# DCI_MCU_Power.net
KiCad netlist of a schematic drawn in Altium Designer
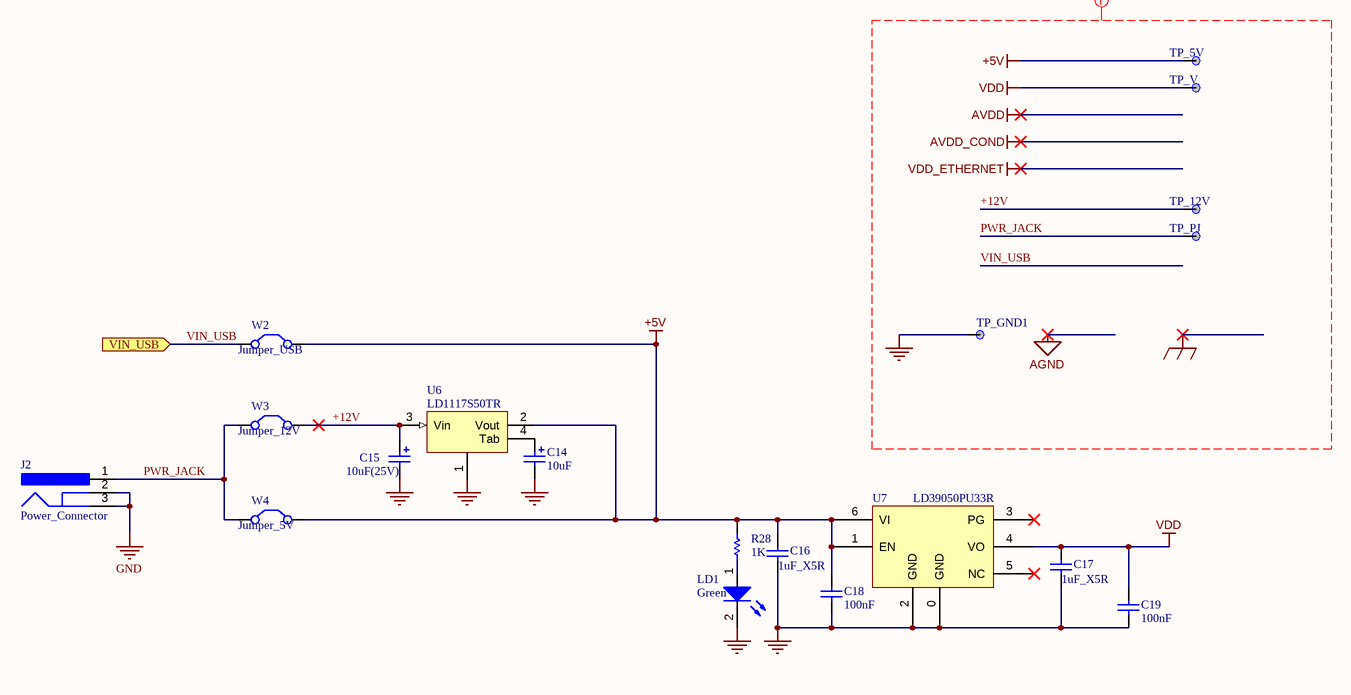
[diagram p0: DCI_MCU_Power.SchDoc]

(export (version "E")
  (design (tool "Eeschema 10.0.6"))
  (components
    (comp (ref "C14")
      (value "10uF")
      (footprint "TAN-A - XDown")
      (description "Polarized Capacitor (Radial)")
      (fields (field (name "PUBLISHER") "Altium Limited"))
      (libsource (lib "Miscellaneous Devices") (part "Cap Pol1"))
    )
    (comp (ref "C15")
      (value "10uF(25V)")
      (footprint "TAN-B")
      (description "Polarized Capacitor (Radial)")
      (fields (field (name "PUBLISHER") "Altium Limited"))
      (libsource (lib "Miscellaneous Devices") (part "Cap Pol1"))
    )
    (comp (ref "C16")
      (value "1uF_X5R")
      (footprint "0603C")
      (description "0603  X5R 1µF")
      (fields (field (name "TOLERANCE") "10%"))
      (libsource (lib "MB963_1") (part "CAP SMD 0603  X5R 1µF 25V 10%"))
    )
    (comp (ref "C17")
      (value "1uF_X5R")
      (footprint "0603C")
      (description "0603  X5R 1µF")
      (fields (field (name "TOLERANCE") "10%"))
      (libsource (lib "MB963_1") (part "CAP SMD 0603  X5R 1µF 25V 10%"))
    )
    (comp (ref "C18")
      (value "100nF")
      (footprint "0603C")
      (description "Capacitor 0402 / 0603 / 0805")
      (libsource (lib "MCD_TOOLS") (part "Capacitor_ST"))
    )
    (comp (ref "C19")
      (value "100nF")
      (footprint "0603C")
      (description "Capacitor 0402 / 0603 / 0805")
      (libsource (lib "MCD_TOOLS") (part "Capacitor_ST"))
    )
    (comp (ref "J2")
      (value "Power_Connector")
      (footprint "CUI-PJ-002AH-4_V")
      (description "DC Power Jack, Right Angle, -25 to 85 degC, 4-Pin 14.8 x 9 x 11 mm SMD, RoHS, Tape and Reel")
      (fields (field (name "MANUFACTURER") "CUIInc.") (field (name "PARTNUMBER") "PJ-002AH"))
      (libsource (lib "Altium Content Vault") (part "JACK-2CD3-RN"))
    )
    (comp (ref "LD1")
      (value "Green")
      (footprint "0603D-G")
      (description "Typical RED, GREEN, YELLOW, AMBER GaAs LED")
      (fields (field (name "PUBLISHER") "Altium Limited"))
      (libsource (lib "Miscellaneous Devices") (part "LED2"))
    )
    (comp (ref "R28")
      (value "1K")
      (footprint "0603R")
      (description "Resistor 0402 / 0603 / 0805")
      (libsource (lib "MCD_TOOLS") (part "Resistor_ST"))
    )
    (comp (ref "TP_5V") (value "TP_5V") (footprint "TP") (libsource (lib "*") (part "TP")))
    (comp (ref "TP_12V") (value "TP_12V") (footprint "TP") (libsource (lib "*") (part "TP")))
    (comp (ref "TP_GND1") (value "TP_GND") (footprint "TP") (libsource (lib "*") (part "TP")))
    (comp (ref "TP_PJ") (value "TP_PJ") (footprint "TP") (libsource (lib "*") (part "TP")))
    (comp (ref "TP_V") (value "TP_VDD") (footprint "TP") (libsource (lib "*") (part "TP")))
    (comp (ref "U6") (value "LD1117S50TR") (footprint "SOT-223") (libsource (lib "MB1137") (part "LD1117")))
    (comp (ref "U7")
      (value "LD39050PU33R")
      (footprint "DFN6_0R95_3x3_TP")
      (libsource (lib "MB1137") (part "LD39050P"))
    )
    (comp (ref "W2")
      (value "Jumper_USB")
      (footprint "RAD-0.2")
      (description "Jumper Wire")
      (fields (field (name "PUBLISHER") "Altium Limited"))
      (libsource (lib "Miscellaneous Devices") (part "Jumper"))
    )
    (comp (ref "W3")
      (value "Jumper_12V")
      (footprint "RAD-0.2")
      (description "Jumper Wire")
      (fields (field (name "PUBLISHER") "Altium Limited"))
      (libsource (lib "Miscellaneous Devices") (part "Jumper"))
    )
    (comp (ref "W4")
      (value "Jumper_5V")
      (footprint "RAD-0.2")
      (description "Jumper Wire")
      (fields (field (name "PUBLISHER") "Altium Limited"))
      (libsource (lib "Miscellaneous Devices") (part "Jumper"))
    )
  )
  (nets
    (net (code "1") (name "+5V") (class "Default")
      (node (ref "C16") (pin "1") (pinfunction "1_1") (pintype "passive"))
      (node (ref "C18") (pin "2") (pinfunction "2_2") (pintype "passive"))
      (node (ref "R28") (pin "2") (pinfunction "2_2") (pintype "passive"))
      (node (ref "TP_5V") (pin "1") (pinfunction "1_1") (pintype "passive"))
      (node (ref "U6") (pin "2") (pinfunction "Vout_2") (pintype "power_in"))
      (node (ref "U7") (pin "1") (pinfunction "EN_1") (pintype "passive"))
      (node (ref "U7") (pin "6") (pinfunction "VI_6") (pintype "passive"))
      (node (ref "W2") (pin "2") (pinfunction "C2_2") (pintype "passive"))
      (node (ref "W4") (pin "2") (pinfunction "C2_2") (pintype "passive"))
    )
    (net (code "2") (name "/+12V") (class "Default")
      (node (ref "C15") (pin "1") (pinfunction "1_1") (pintype "passive"))
      (node (ref "TP_12V") (pin "1") (pinfunction "1_1") (pintype "passive"))
      (node (ref "U6") (pin "3") (pinfunction "Vin_3") (pintype "input"))
      (node (ref "W3") (pin "2") (pinfunction "C2_2") (pintype "passive"))
    )
    (net (code "3") (name "/PWR_JACK") (class "Default")
      (node (ref "J2") (pin "1") (pinfunction "1_1") (pintype "passive"))
      (node (ref "TP_PJ") (pin "1") (pinfunction "1_1") (pintype "passive"))
      (node (ref "W3") (pin "1") (pinfunction "C1_1") (pintype "passive"))
      (node (ref "W4") (pin "1") (pinfunction "C1_1") (pintype "passive"))
    )
    (net (code "4") (name "/VIN_USB") (class "Default")
      (node (ref "W2") (pin "1") (pinfunction "C1_1") (pintype "passive"))
    )
    (net (code "9") (name "GND") (class "Default")
      (node (ref "C14") (pin "2") (pinfunction "2_2") (pintype "passive"))
      (node (ref "C15") (pin "2") (pinfunction "2_2") (pintype "passive"))
      (node (ref "C16") (pin "2") (pinfunction "2_2") (pintype "passive"))
      (node (ref "C17") (pin "2") (pinfunction "2_2") (pintype "passive"))
      (node (ref "C18") (pin "1") (pinfunction "1_1") (pintype "passive"))
      (node (ref "C19") (pin "1") (pinfunction "1_1") (pintype "passive"))
      (node (ref "J2") (pin "2") (pinfunction "2_2") (pintype "passive"))
      (node (ref "J2") (pin "3") (pinfunction "3_3") (pintype "passive"))
      (node (ref "LD1") (pin "2") (pinfunction "K_2") (pintype "passive"))
      (node (ref "TP_GND1") (pin "1") (pinfunction "1_1") (pintype "passive"))
      (node (ref "U6") (pin "1") (pintype "passive"))
      (node (ref "U7") (pin "0") (pinfunction "GND_0") (pintype "passive"))
      (node (ref "U7") (pin "2") (pinfunction "GND_2") (pintype "passive"))
    )
    (net (code "10") (name "Net-(LD1-A)") (class "Default")
      (node (ref "LD1") (pin "1") (pinfunction "A_1") (pintype "passive"))
      (node (ref "R28") (pin "1") (pinfunction "1_1") (pintype "passive"))
    )
    (net (code "11") (name "Net-(U6-Tab)") (class "Default")
      (node (ref "C14") (pin "1") (pinfunction "1_1") (pintype "passive"))
      (node (ref "U6") (pin "4") (pinfunction "Tab_4") (pintype "power_in"))
    )
    (net (code "12") (name "VDD") (class "Default")
      (node (ref "C17") (pin "1") (pinfunction "1_1") (pintype "passive"))
      (node (ref "C19") (pin "2") (pinfunction "2_2") (pintype "passive"))
      (node (ref "TP_V") (pin "1") (pinfunction "1_1") (pintype "passive"))
      (node (ref "U7") (pin "4") (pinfunction "VO_4") (pintype "passive"))
    )
    (net (code "14") (name "unconnected-(U7-NC-Pad5)") (class "Default")
      (node (ref "U7") (pin "5") (pinfunction "NC_5") (pintype "passive+no_connect"))
    )
    (net (code "15") (name "unconnected-(U7-PG-Pad3)") (class "Default")
      (node (ref "U7") (pin "3") (pinfunction "PG_3") (pintype "passive+no_connect"))
    )
  )
)
